# CAN_module.net
KiCad netlist of a schematic drawn in EAGLE
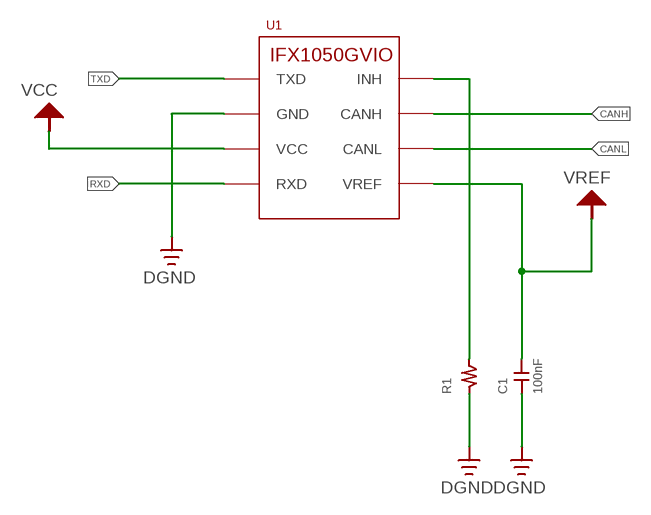
[diagram p0: schematic, sheet 1]

(export (version "E")
  (design (tool "Eeschema 10.0.6"))
  (components
    (comp (ref "C1")
      (value "100nF")
      (footprint "eagle-import:2012")
      (libsource (lib "eagle-import") (part "CAPACITOR_CHIP2012"))
    )
    (comp (ref "R1")
      (value "RESISTOR_CHIP_2012")
      (footprint "eagle-import:2012")
      (libsource (lib "eagle-import") (part "RESISTOR_CHIP_2012"))
    )
    (comp (ref "U1")
      (value "IFX1050GVIO")
      (footprint "eagle-import:PG-DSO-8")
      (libsource (lib "eagle-import") (part "IFX1050GVIO"))
    )
  )
  (nets
    (net (code "1") (name "CANH") (class "Default")
      (node (ref "U1") (pin "P7") (pinfunction "CANH_P7") (pintype "bidirectional"))
    )
    (net (code "2") (name "CANL") (class "Default")
      (node (ref "U1") (pin "P6") (pinfunction "CANL_P6") (pintype "bidirectional"))
    )
    (net (code "3") (name "DGND") (class "Default")
      (node (ref "C1") (pin "P$1") (pinfunction "P$1_P$1") (pintype "passive"))
      (node (ref "R1") (pin "P$1") (pinfunction "P$1_P$1") (pintype "passive"))
      (node (ref "U1") (pin "P2") (pinfunction "GND_P2") (pintype "power_in"))
    )
    (net (code "4") (name "Net-(U1-INH)") (class "Default")
      (node (ref "R1") (pin "P$2") (pinfunction "P$2_P$2") (pintype "passive"))
      (node (ref "U1") (pin "P8") (pinfunction "INH_P8") (pintype "bidirectional"))
    )
    (net (code "5") (name "RXD") (class "Default")
      (node (ref "U1") (pin "P4") (pinfunction "RXD_P4") (pintype "bidirectional"))
    )
    (net (code "6") (name "TXD") (class "Default")
      (node (ref "U1") (pin "P1") (pinfunction "TXD_P1") (pintype "bidirectional"))
    )
    (net (code "7") (name "VCC") (class "Default")
      (node (ref "U1") (pin "P3") (pinfunction "VCC_P3") (pintype "power_in"))
    )
    (net (code "8") (name "VREF") (class "Default")
      (node (ref "C1") (pin "P$2") (pinfunction "P$2_P$2") (pintype "passive"))
      (node (ref "U1") (pin "P5") (pinfunction "VREF_P5") (pintype "power_in"))
    )
  )
)
